# RT9193.net
KiCad netlist of a schematic drawn in Altium Designer
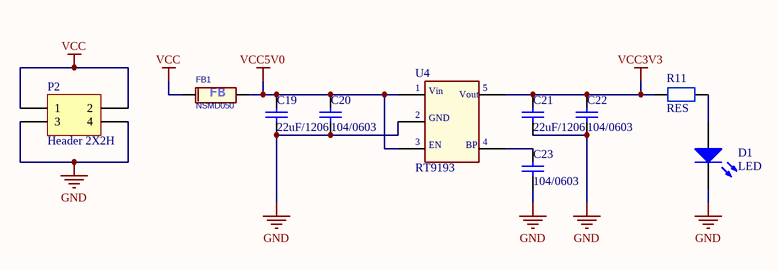
[diagram p0: RT9193.SchDoc]

(export (version "E")
  (design (tool "Eeschema 10.0.6"))
  (components
    (comp (ref "C19")
      (value "22uF/1206")
      (footprint "C1206")
      (description "无极性贴片电容")
      (libsource (lib "常用原件") (part "CAP"))
    )
    (comp (ref "C20")
      (value "104/0603")
      (footprint "C1206")
      (description "无极性贴片电容")
      (libsource (lib "常用原件") (part "CAP"))
    )
    (comp (ref "C21")
      (value "22uF/1206")
      (footprint "C1206")
      (description "无极性贴片电容")
      (libsource (lib "常用原件") (part "CAP"))
    )
    (comp (ref "C22")
      (value "104/0603")
      (footprint "C1206")
      (description "无极性贴片电容")
      (libsource (lib "常用原件") (part "CAP"))
    )
    (comp (ref "C23")
      (value "104/0603")
      (footprint "C1206")
      (description "无极性贴片电容")
      (libsource (lib "常用原件") (part "CAP"))
    )
    (comp (ref "D1") (value "LED") (footprint "LED0805") (libsource (lib "常用原件") (part "LED")))
    (comp (ref "FB1")
      (value "NSMD050")
      (footprint "R1206")
      (description "Ferrite Beads Inductors Impedance:120Ω±25% Rated Current:1500mA DC Resistance:0.095Ω")
      (fields
        (field (name "MANUFACTURER") "muRata")
        (field (name "MANUFACTURER PART NUMBER") "BLM15EG121SN1")
      )
      (libsource (lib "JLINK-OB_V1.0") (part "FB"))
    )
    (comp (ref "P2")
      (value "Header 2X2H")
      (footprint "HDR2X2H")
      (description "Header, 2-Pin, Dual row, Right Angle")
      (fields (field (name "PUBLISHER") "Altium Limited"))
      (libsource (lib "Miscellaneous Connectors") (part "Header 2X2H"))
    )
    (comp (ref "R11") (value "RES") (footprint "R0603") (libsource (lib "常用原件") (part "RES")))
    (comp (ref "U4")
      (value "RT9193")
      (footprint "SOT-23-5")
      (description "RT9193-1.2, RT9193-1.8, RT9193-3.3")
      (libsource (lib "JLINK-OB_V1.0") (part "RT9193"))
    )
  )
  (nets
    (net (code "1") (name "GND") (class "Default")
      (node (ref "C19") (pin "1") (pinfunction "1_1") (pintype "passive"))
      (node (ref "C20") (pin "1") (pinfunction "1_1") (pintype "passive"))
      (node (ref "C21") (pin "1") (pinfunction "1_1") (pintype "passive"))
      (node (ref "C22") (pin "1") (pinfunction "1_1") (pintype "passive"))
      (node (ref "C23") (pin "1") (pinfunction "1_1") (pintype "passive"))
      (node (ref "D1") (pin "1") (pinfunction "K_1") (pintype "passive"))
      (node (ref "P2") (pin "3") (pinfunction "3_3") (pintype "passive"))
      (node (ref "P2") (pin "4") (pinfunction "4_4") (pintype "passive"))
      (node (ref "U4") (pin "2") (pinfunction "GND_2") (pintype "passive"))
    )
    (net (code "2") (name "Net-(D1-A)") (class "Default")
      (node (ref "D1") (pin "2") (pinfunction "A_2") (pintype "passive"))
      (node (ref "R11") (pin "1") (pinfunction "1_1") (pintype "passive"))
    )
    (net (code "3") (name "Net-(U4-BP)") (class "Default")
      (node (ref "C23") (pin "2") (pinfunction "2_2") (pintype "passive"))
      (node (ref "U4") (pin "4") (pinfunction "BP_4") (pintype "passive"))
    )
    (net (code "4") (name "VCC") (class "Default")
      (node (ref "FB1") (pin "1") (pinfunction "1_1") (pintype "passive"))
      (node (ref "P2") (pin "1") (pinfunction "1_1") (pintype "passive"))
      (node (ref "P2") (pin "2") (pinfunction "2_2") (pintype "passive"))
    )
    (net (code "5") (name "VCC3V3") (class "Default")
      (node (ref "C21") (pin "2") (pinfunction "2_2") (pintype "passive"))
      (node (ref "C22") (pin "2") (pinfunction "2_2") (pintype "passive"))
      (node (ref "R11") (pin "2") (pinfunction "2_2") (pintype "passive"))
      (node (ref "U4") (pin "5") (pinfunction "Vout_5") (pintype "passive"))
    )
    (net (code "6") (name "VCC5V0") (class "Default")
      (node (ref "C19") (pin "2") (pinfunction "2_2") (pintype "passive"))
      (node (ref "C20") (pin "2") (pinfunction "2_2") (pintype "passive"))
      (node (ref "FB1") (pin "2") (pinfunction "2_2") (pintype "passive"))
      (node (ref "U4") (pin "1") (pinfunction "Vin_1") (pintype "passive"))
      (node (ref "U4") (pin "3") (pinfunction "SHDN_3") (pintype "passive"))
    )
  )
)
